# CTR_USB.net
KiCad netlist of a schematic drawn in Altium Designer
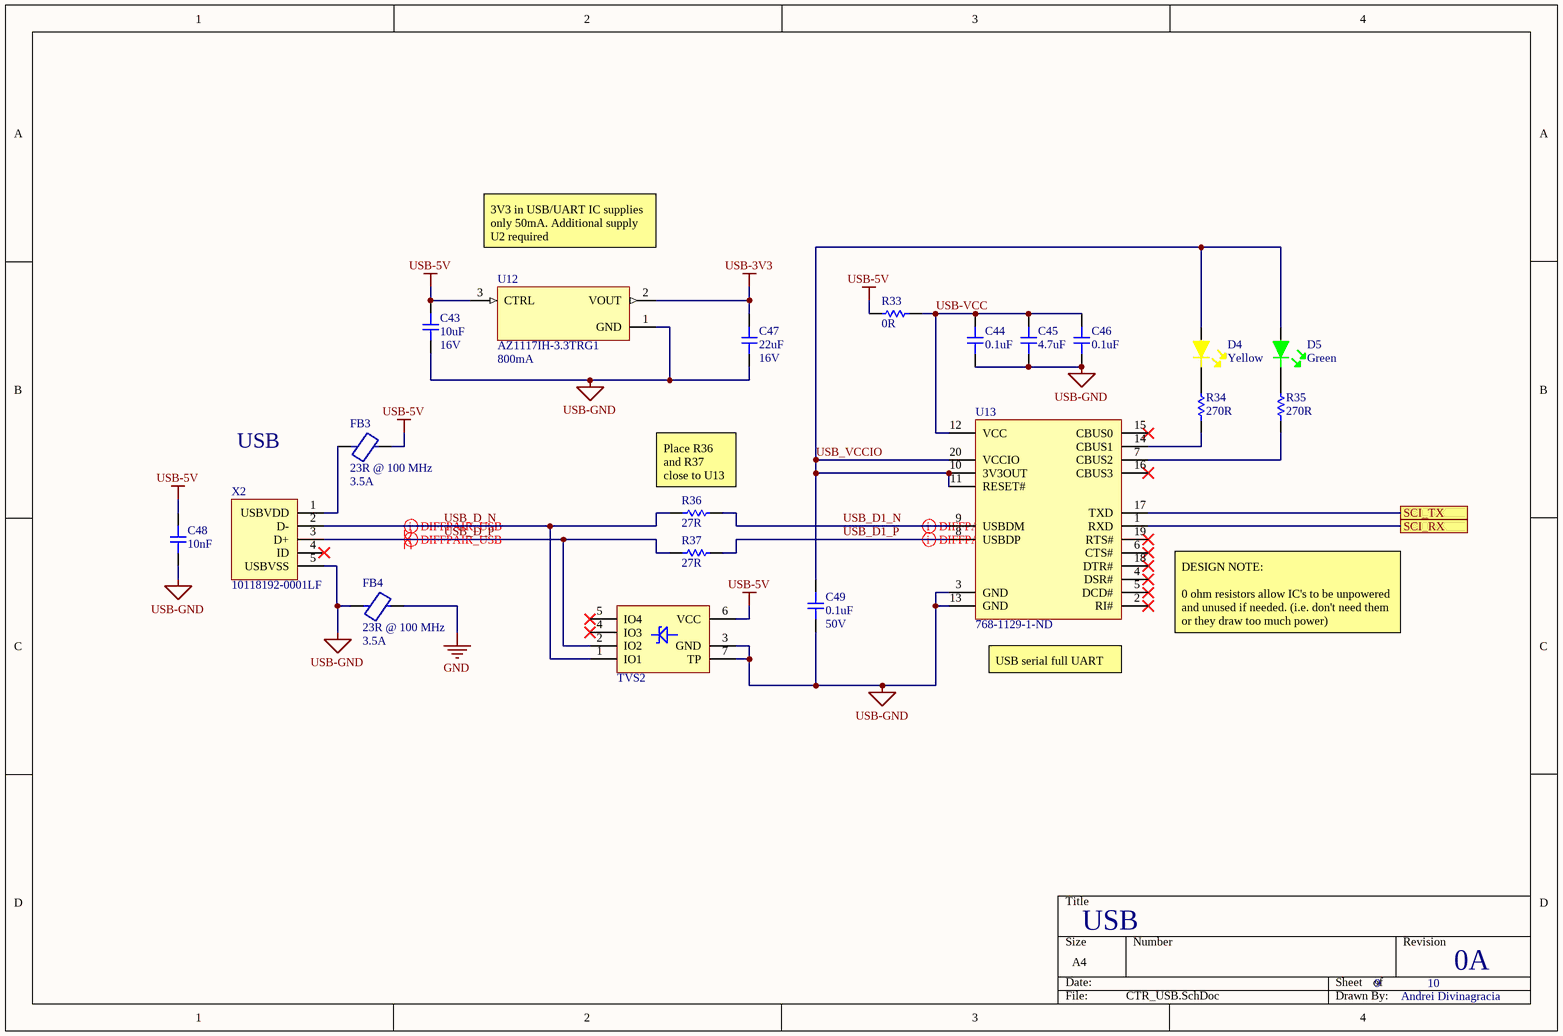
[diagram p0: CTR_USB.SchDoc]

(export (version "E")
  (design (tool "Eeschema 10.0.6"))
  (components
    (comp (ref "C43")
      (value "10uF")
      (footprint "CAP-0805")
      (description "CAP CER 10UF 16V X5R 0805")
      (fields
        (field (name "MANUFACTURER") "Samsung")
        (field (name "MANUFACTURER PART NUMBER") "CL21A106KOQNNNE")
        (field (name "VOLTAGE") "16V")
      )
      (libsource (lib "InverterSCHLib") (part "0805-10uF-16V"))
    )
    (comp (ref "C44")
      (value "0.1uF")
      (footprint "CAP-0805")
      (description "CAP CER 0.1UF 50V Y5V 0805")
      (fields
        (field (name "MANUFACTURER") "KEMET")
        (field (name "MANUFACTURER PART NUMBER") "C0805C104Z5VACTU")
      )
      (libsource (lib "InverterSCHLib") (part "0805-0.1uF-50V"))
    )
    (comp (ref "C45")
      (value "4.7uF")
      (footprint "CAP-1206")
      (description "CAP CER 4.7UF 50V X7R 1206")
      (fields
        (field (name "MANUFACTURER") "TDK")
        (field (name "MANUFACTURER PART NUMBER") "C3216X7R1H475K160AC")
      )
      (libsource (lib "InverterSCHLib") (part "1206-4.7uF-50V"))
    )
    (comp (ref "C46")
      (value "0.1uF")
      (footprint "CAP-0805")
      (description "CAP CER 0.1UF 50V Y5V 0805")
      (fields
        (field (name "MANUFACTURER") "KEMET")
        (field (name "MANUFACTURER PART NUMBER") "C0805C104Z5VACTU")
      )
      (libsource (lib "InverterSCHLib") (part "0805-0.1uF-50V"))
    )
    (comp (ref "C47")
      (value "22uF")
      (footprint "CAP-0805")
      (description "CAP CER 22UF 16V X5R 0805")
      (fields
        (field (name "MANUFACTURER") "Samsung")
        (field (name "MANUFACTURER PART NUMBER") "CL21A226KOQNNNE")
        (field (name "VOLTAGE RATING") "16V")
      )
      (libsource (lib "InverterSCHLib") (part "0805-22uF-16V"))
    )
    (comp (ref "C48")
      (value "10nF")
      (footprint "CAP-0805")
      (description "CAP CER SMD 0805 .01UF X7R 5% 50V")
      (fields
        (field (name "MANUFACTURER") "KEMET")
        (field (name "MANUFACTURER PART NUMBER") "C0805C103J5RAC7210")
      )
      (libsource (lib "InverterSCHLib") (part "0805-10nF-50V"))
    )
    (comp (ref "C49")
      (value "0.1uF")
      (footprint "CAP-0603")
      (description "CAP CER 0.1UF 50V X7R 0603")
      (fields
        (field (name "MANUFACTURER") "Samsung")
        (field (name "MANUFACTURER PART NUMBER") "CL10B104KB8NNNL")
        (field (name "VOLTAGE RATING") "50V")
      )
      (libsource (lib "InverterSCHLib") (part "0603-0.1uF-50V"))
    )
    (comp (ref "D4")
      (value "Yellow")
      (footprint "LED-0603")
      (description "LED YELLOW CLEAR 0603 SMD")
      (fields
        (field (name "MANUFACTURER") "Wurth Electronics")
        (field (name "MANUFACTURER PART NUMBER") "150060YS75000")
      )
      (libsource (lib "InverterSCHLib") (part "LED-YELLOW"))
    )
    (comp (ref "D5")
      (value "Green")
      (footprint "LED-0603")
      (description "LED GREEN CLEAR 0603 SMD")
      (fields
        (field (name "MANUFACTURER") "Wurth Electronics")
        (field (name "MANUFACTURER PART NUMBER") "150060VS75000")
      )
      (libsource (lib "InverterSCHLib") (part "LED-Green"))
    )
    (comp (ref "FB3")
      (value "23R @ 100 MHz")
      (footprint "FB-1806")
      (description "FERRITE BEAD 23 OHM 1806 1LN")
      (fields
        (field (name "MANUFACTURER") "Taiyo Yuden")
        (field (name "MANUFACTURER PART NUMBER") "FBMJ4516HL230NTV")
        (field (name "MAX CURRENT RATING") "3.5A")
      )
      (libsource (lib "InverterSCHLib") (part "FERR-3A5"))
    )
    (comp (ref "FB4")
      (value "23R @ 100 MHz")
      (footprint "FB-1806")
      (description "FERRITE BEAD 23 OHM 1806 1LN")
      (fields
        (field (name "MANUFACTURER") "Taiyo Yuden")
        (field (name "MANUFACTURER PART NUMBER") "FBMJ4516HL230NTV")
        (field (name "MAX CURRENT RATING") "3.5A")
      )
      (libsource (lib "InverterSCHLib") (part "FERR-3A5"))
    )
    (comp (ref "R33")
      (value "0R")
      (footprint "RES-0603")
      (description "RES SMD 0 OHM JUMPER 1/10W 0603")
      (fields
        (field (name "MANUFACTURER") "Yageo")
        (field (name "MANUFACTURER PART NUMBER") "RC0603JR-070RL")
      )
      (libsource (lib "InverterSCHLib") (part "0603-0R"))
    )
    (comp (ref "R34")
      (value "270R")
      (footprint "RES-0603")
      (description "RES SMD 270 OHM 0.5% 1/10W 0603")
      (fields
        (field (name "MANUFACTURER") "Yageo")
        (field (name "MANUFACTURER PART NUMBER") "RT0603DRE07270RL")
      )
      (libsource (lib "InverterSCHLib") (part "0603-270R"))
    )
    (comp (ref "R35")
      (value "270R")
      (footprint "RES-0603")
      (description "RES SMD 270 OHM 0.5% 1/10W 0603")
      (fields
        (field (name "MANUFACTURER") "Yageo")
        (field (name "MANUFACTURER PART NUMBER") "RT0603DRE07270RL")
      )
      (libsource (lib "InverterSCHLib") (part "0603-270R"))
    )
    (comp (ref "R36")
      (value "27R")
      (footprint "RES-0603")
      (description "RES SMD 27 OHM 5% 1/10W 0603")
      (fields
        (field (name "MANUFACTURER") "Panasonic")
        (field (name "MANUFACTURER PART NUMBER") "ERJ-3GEYJ270V")
      )
      (libsource (lib "InverterSCHLib") (part "0603-27R"))
    )
    (comp (ref "R37")
      (value "27R")
      (footprint "RES-0603")
      (description "RES SMD 27 OHM 5% 1/10W 0603")
      (fields
        (field (name "MANUFACTURER") "Panasonic")
        (field (name "MANUFACTURER PART NUMBER") "ERJ-3GEYJ270V")
      )
      (libsource (lib "InverterSCHLib") (part "0603-27R"))
    )
    (comp (ref "TVS2")
      (value "TVS-4-5.5V-Bi")
      (footprint "TVS-DRS-TP-5")
      (description "TVS DIODE 5.5V 6SON")
      (fields
        (field (name "MANUFACTURER") "Texas Instruments")
        (field (name "MANUFACTURER PART NUMBER") "TPD4E001DRSR")
      )
      (libsource (lib "InverterSCHLib") (part "TVS-4-5.5V-Bi"))
    )
    (comp (ref "U12")
      (value "AZ1117IH-3.3TRG1")
      (footprint "SOT223")
      (description "IC REG LINEAR 3.3V 1A SOT223")
      (fields (field (name "MANUFACTURER") "Diodes") (field (name "OUTPUT CURRENT") "800mA"))
      (libsource (lib "InverterSCHLib") (part "AZ1117IH-3.3TRG1"))
    )
    (comp (ref "U13")
      (value "768-1129-1-ND")
      (footprint "SSOP-20")
      (description "IC USB SERIAL FULL UART 20SSOP")
      (fields (field (name "MANUFACTURER") "FTDI") (field (name "MANUFACTURER PART NUMBER") "FT231XS-R"))
      (libsource (lib "InverterSCHLib") (part "FT231XS-R"))
    )
    (comp (ref "X2")
      (value "10118192-0001LF")
      (footprint "USB_MICRO")
      (description "CONN_USB - micro B USB 2.0 Receptacle Connector 5 Position Surface Mount, Right Angle, Horizontal")
      (fields (field (name "MANUFACTURER") "Amphenol FCI"))
      (libsource (lib "InverterSCHLib") (part "CONN-USB"))
    )
  )
  (nets
    (net (code "1") (name "/SCI_RX") (class "Default")
      (node (ref "U13") (pin "1") (pinfunction "RXD_1") (pintype "passive"))
    )
    (net (code "2") (name "/SCI_TX") (class "Default")
      (node (ref "U13") (pin "17") (pinfunction "TXD_17") (pintype "passive"))
    )
    (net (code "3") (name "/USB-VCC") (class "Default")
      (node (ref "C44") (pin "2") (pinfunction "2_2") (pintype "passive"))
      (node (ref "C45") (pin "2") (pinfunction "2_2") (pintype "passive"))
      (node (ref "C46") (pin "2") (pinfunction "2_2") (pintype "passive"))
      (node (ref "R33") (pin "1") (pinfunction "1_1") (pintype "passive"))
      (node (ref "U13") (pin "12") (pinfunction "VCC_12") (pintype "passive"))
    )
    (net (code "4") (name "/USB_D1_N") (class "Default")
      (node (ref "R36") (pin "2") (pinfunction "2_2") (pintype "passive"))
      (node (ref "U13") (pin "9") (pinfunction "USBDM_9") (pintype "passive"))
    )
    (net (code "5") (name "/USB_D1_P") (class "Default")
      (node (ref "R37") (pin "2") (pinfunction "2_2") (pintype "passive"))
      (node (ref "U13") (pin "8") (pinfunction "USBDP_8") (pintype "passive"))
    )
    (net (code "6") (name "/USB_D_N") (class "Default")
      (node (ref "R36") (pin "1") (pinfunction "1_1") (pintype "passive"))
      (node (ref "TVS2") (pin "1") (pinfunction "IO1_1") (pintype "passive"))
      (node (ref "X2") (pin "2") (pinfunction "D-_2") (pintype "passive"))
    )
    (net (code "7") (name "/USB_D_P") (class "Default")
      (node (ref "R37") (pin "1") (pinfunction "1_1") (pintype "passive"))
      (node (ref "TVS2") (pin "2") (pinfunction "IO2_2") (pintype "passive"))
      (node (ref "X2") (pin "3") (pinfunction "D+_3") (pintype "passive"))
    )
    (net (code "8") (name "/USB_VCCIO") (class "Default")
      (node (ref "C49") (pin "2") (pinfunction "2_2") (pintype "passive"))
      (node (ref "D4") (pin "1") (pinfunction "1_1") (pintype "passive"))
      (node (ref "D5") (pin "1") (pinfunction "1_1") (pintype "passive"))
      (node (ref "U13") (pin "10") (pinfunction "3V3OUT_10") (pintype "passive"))
      (node (ref "U13") (pin "11") (pinfunction "RESET#_11") (pintype "passive"))
      (node (ref "U13") (pin "20") (pinfunction "VCCIO_20") (pintype "passive"))
    )
    (net (code "9") (name "GND") (class "Default")
      (node (ref "FB4") (pin "2") (pinfunction "2_2") (pintype "passive"))
    )
    (net (code "10") (name "Net-(D4-Pad2)") (class "Default")
      (node (ref "D4") (pin "2") (pinfunction "2_2") (pintype "passive"))
      (node (ref "R34") (pin "2") (pinfunction "2_2") (pintype "passive"))
    )
    (net (code "11") (name "Net-(D5-Pad2)") (class "Default")
      (node (ref "D5") (pin "2") (pinfunction "2_2") (pintype "passive"))
      (node (ref "R35") (pin "2") (pinfunction "2_2") (pintype "passive"))
    )
    (net (code "12") (name "Net-(U13-CBUS1)") (class "Default")
      (node (ref "R34") (pin "1") (pinfunction "1_1") (pintype "passive"))
      (node (ref "U13") (pin "14") (pinfunction "CBUS1_14") (pintype "passive"))
    )
    (net (code "13") (name "Net-(U13-CBUS2)") (class "Default")
      (node (ref "R35") (pin "1") (pinfunction "1_1") (pintype "passive"))
      (node (ref "U13") (pin "7") (pinfunction "CBUS2_7") (pintype "passive"))
    )
    (net (code "14") (name "Net-(X2-USBVDD)") (class "Default")
      (node (ref "FB3") (pin "1") (pinfunction "1_1") (pintype "passive"))
      (node (ref "X2") (pin "1") (pinfunction "USBVDD_1") (pintype "passive"))
    )
    (net (code "15") (name "USB-3V3") (class "Default")
      (node (ref "C47") (pin "2") (pinfunction "2_2") (pintype "passive"))
      (node (ref "U12") (pin "2") (pinfunction "VOUT_2") (pintype "output"))
    )
    (net (code "16") (name "USB-5V") (class "Default")
      (node (ref "C43") (pin "2") (pinfunction "2_2") (pintype "passive"))
      (node (ref "C48") (pin "1") (pinfunction "1_1") (pintype "passive"))
      (node (ref "FB3") (pin "2") (pinfunction "2_2") (pintype "passive"))
      (node (ref "R33") (pin "2") (pinfunction "2_2") (pintype "passive"))
      (node (ref "TVS2") (pin "6") (pinfunction "VCC_6") (pintype "passive"))
      (node (ref "U12") (pin "3") (pinfunction "CTRL_3") (pintype "input"))
    )
    (net (code "17") (name "USB-GND") (class "Default")
      (node (ref "C43") (pin "1") (pinfunction "1_1") (pintype "passive"))
      (node (ref "C44") (pin "1") (pinfunction "1_1") (pintype "passive"))
      (node (ref "C45") (pin "1") (pinfunction "1_1") (pintype "passive"))
      (node (ref "C46") (pin "1") (pinfunction "1_1") (pintype "passive"))
      (node (ref "C47") (pin "1") (pinfunction "1_1") (pintype "passive"))
      (node (ref "C48") (pin "2") (pinfunction "2_2") (pintype "passive"))
      (node (ref "C49") (pin "1") (pinfunction "1_1") (pintype "passive"))
      (node (ref "FB4") (pin "1") (pinfunction "1_1") (pintype "passive"))
      (node (ref "TVS2") (pin "3") (pinfunction "GND_3") (pintype "passive"))
      (node (ref "TVS2") (pin "7") (pinfunction "TP_7") (pintype "passive"))
      (node (ref "U12") (pin "1") (pinfunction "GND_1") (pintype "passive"))
      (node (ref "U13") (pin "13") (pinfunction "GND_13") (pintype "passive"))
      (node (ref "U13") (pin "3") (pinfunction "GND_3") (pintype "passive"))
      (node (ref "X2") (pin "5") (pinfunction "USBVSS_5") (pintype "passive"))
    )
    (net (code "18") (name "unconnected-(TVS2-IO3-Pad4)") (class "Default")
      (node (ref "TVS2") (pin "4") (pinfunction "IO3_4") (pintype "passive+no_connect"))
    )
    (net (code "19") (name "unconnected-(TVS2-IO4-Pad5)") (class "Default")
      (node (ref "TVS2") (pin "5") (pinfunction "IO4_5") (pintype "passive+no_connect"))
    )
    (net (code "20") (name "unconnected-(U13-CBUS0-Pad15)") (class "Default")
      (node (ref "U13") (pin "15") (pinfunction "CBUS0_15") (pintype "passive+no_connect"))
    )
    (net (code "21") (name "unconnected-(U13-CBUS3-Pad16)") (class "Default")
      (node (ref "U13") (pin "16") (pinfunction "CBUS3_16") (pintype "passive+no_connect"))
    )
    (net (code "22") (name "unconnected-(U13-CTS#-Pad6)") (class "Default")
      (node (ref "U13") (pin "6") (pinfunction "CTS#_6") (pintype "passive+no_connect"))
    )
    (net (code "23") (name "unconnected-(U13-DCD#-Pad5)") (class "Default")
      (node (ref "U13") (pin "5") (pinfunction "DCD#_5") (pintype "passive+no_connect"))
    )
    (net (code "24") (name "unconnected-(U13-DSR#-Pad4)") (class "Default")
      (node (ref "U13") (pin "4") (pinfunction "DSR#_4") (pintype "passive+no_connect"))
    )
    (net (code "25") (name "unconnected-(U13-DTR#-Pad18)") (class "Default")
      (node (ref "U13") (pin "18") (pinfunction "DTR#_18") (pintype "passive+no_connect"))
    )
    (net (code "26") (name "unconnected-(U13-RI#-Pad2)") (class "Default")
      (node (ref "U13") (pin "2") (pinfunction "RI#_2") (pintype "passive+no_connect"))
    )
    (net (code "27") (name "unconnected-(U13-RTS#-Pad19)") (class "Default")
      (node (ref "U13") (pin "19") (pinfunction "RTS#_19") (pintype "passive+no_connect"))
    )
    (net (code "28") (name "unconnected-(X2-ID-Pad4)") (class "Default")
      (node (ref "X2") (pin "4") (pinfunction "ID_4") (pintype "passive+no_connect"))
    )
  )
)
